# pwrmeas.net
KiCad netlist of a schematic drawn in Altium Designer
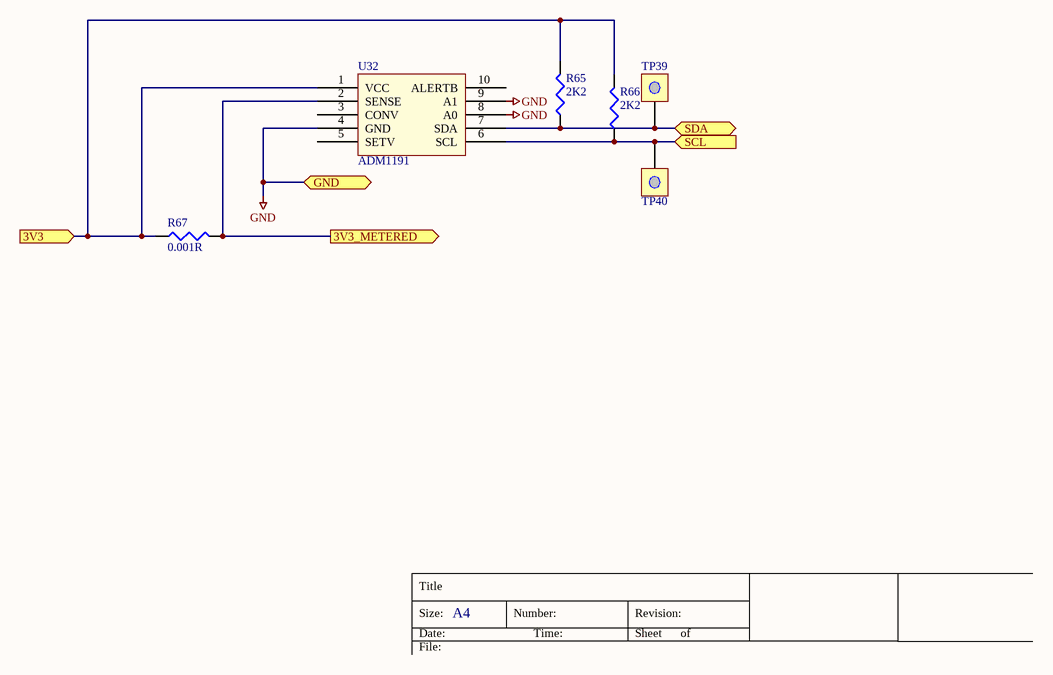
[diagram p0: pwrmeas.SchDoc]

(export (version "E")
  (design (tool "Eeschema 10.0.6"))
  (components
    (comp (ref "R65")
      (value "2K2")
      (footprint "0603")
      (description "Resistor")
      (libsource (lib "RCLDQ") (part "RES1"))
    )
    (comp (ref "R66")
      (value "2K2")
      (footprint "0603")
      (description "Resistor")
      (libsource (lib "RCLDQ") (part "RES1"))
    )
    (comp (ref "R67")
      (value "0.001R")
      (footprint "CRA2512")
      (description "Resistor")
      (libsource (lib "RCLDQ") (part "RES1"))
    )
    (comp (ref "TP39")
      (value "SDA")
      (footprint "TESTPOINT")
      (description "TEST POINT")
      (libsource (lib "") (part "TEST_1"))
    )
    (comp (ref "TP40")
      (value "SCL")
      (footprint "TESTPOINT")
      (description "TEST POINT")
      (libsource (lib "Miscellaneous") (part "TEST"))
    )
    (comp (ref "U32")
      (value "ADM1191")
      (footprint "MSOP10")
      (description "Digital I2C Power Monitor")
      (libsource (lib "sion") (part "ADM1191"))
    )
  )
  (nets
    (net (code "1") (name "/3V3") (class "Default")
      (node (ref "R65") (pin "2") (pinfunction "2_2") (pintype "passive"))
      (node (ref "R66") (pin "2") (pinfunction "2_2") (pintype "passive"))
      (node (ref "R67") (pin "1") (pinfunction "1_1") (pintype "passive"))
      (node (ref "U32") (pin "1") (pinfunction "VCC_1") (pintype "passive"))
    )
    (net (code "2") (name "/3V3_METERED") (class "Default")
      (node (ref "R67") (pin "2") (pinfunction "2_2") (pintype "passive"))
      (node (ref "U32") (pin "2") (pinfunction "SENSE_2") (pintype "passive"))
    )
    (net (code "3") (name "/SCL") (class "Default")
      (node (ref "R66") (pin "1") (pinfunction "1_1") (pintype "passive"))
      (node (ref "TP40") (pin "0") (pinfunction "TP_0") (pintype "passive"))
      (node (ref "U32") (pin "6") (pinfunction "SCL_6") (pintype "passive"))
    )
    (net (code "4") (name "/SDA") (class "Default")
      (node (ref "R65") (pin "1") (pinfunction "1_1") (pintype "passive"))
      (node (ref "TP39") (pin "0") (pinfunction "TP_0") (pintype "passive"))
      (node (ref "U32") (pin "7") (pinfunction "SDA_7") (pintype "passive"))
    )
    (net (code "5") (name "GND") (class "Default")
      (node (ref "U32") (pin "4") (pinfunction "GND_4") (pintype "passive"))
      (node (ref "U32") (pin "8") (pinfunction "A0_8") (pintype "passive"))
      (node (ref "U32") (pin "9") (pinfunction "A1_9") (pintype "passive"))
    )
    (net (code "6") (name "unconnected-(U32-ALERTB-Pad10)") (class "Default")
      (node (ref "U32") (pin "10") (pinfunction "ALERTB_10") (pintype "passive"))
    )
    (net (code "7") (name "unconnected-(U32-CONV-Pad3)") (class "Default")
      (node (ref "U32") (pin "3") (pinfunction "CONV_3") (pintype "passive"))
    )
    (net (code "8") (name "unconnected-(U32-SETV-Pad5)") (class "Default")
      (node (ref "U32") (pin "5") (pinfunction "SETV_5") (pintype "passive"))
    )
  )
)
